# 5-Connector.net
KiCad netlist of a schematic drawn in Altium Designer
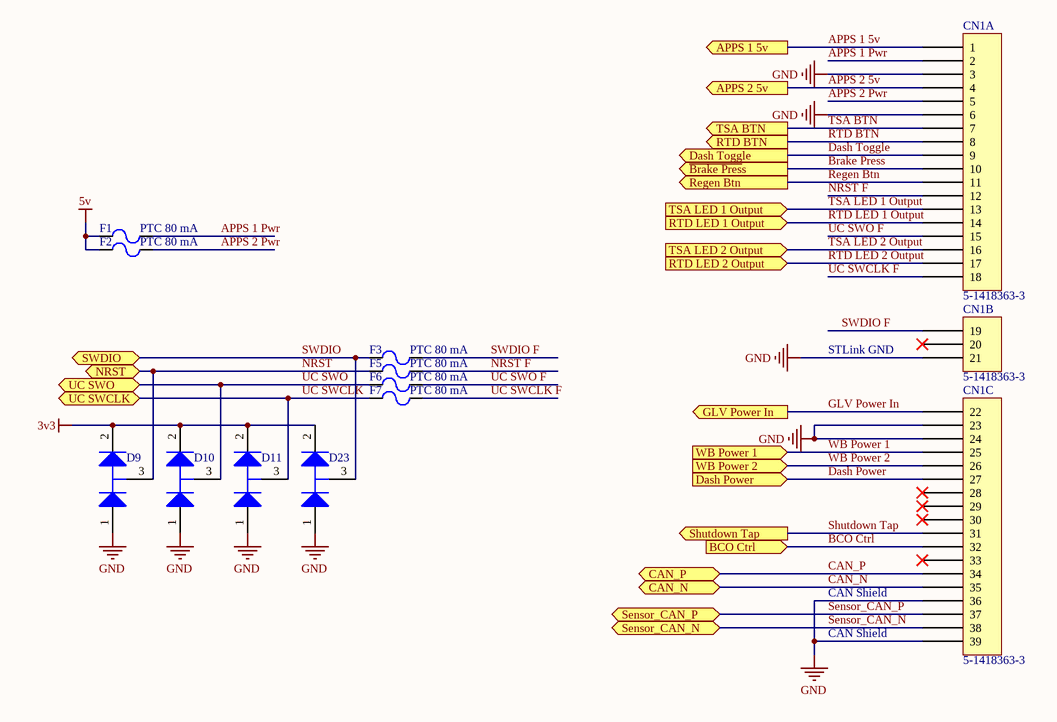
[diagram p0: 5-Connector.SchDoc]

(export (version "E")
  (design (tool "Eeschema 10.0.6"))
  (components
    (comp (ref "CN1")
      (value "5-1418363-3")
      (footprint "5-1418363-3")
      (description "Levyseal 90 degree 39 pin header")
      (libsource (lib "VCB20") (part "5-1418363-3"))
    )
    (comp (ref "D9")
      (value "SZNUP1301ML3T1G")
      (footprint "ONSC-SOT-23-3-318-08_V")
      (fields (field (name "MANUFACTURER") "On Semiconductor"))
      (libsource (lib "Altium Content Vault") (part "ONSC-NUP1301-SOT-23-3-318-08"))
    )
    (comp (ref "D10")
      (value "SZNUP1301ML3T1G")
      (footprint "ONSC-SOT-23-3-318-08_V")
      (fields (field (name "MANUFACTURER") "On Semiconductor"))
      (libsource (lib "Altium Content Vault") (part "ONSC-NUP1301-SOT-23-3-318-08"))
    )
    (comp (ref "D11")
      (value "SZNUP1301ML3T1G")
      (footprint "ONSC-SOT-23-3-318-08_V")
      (fields (field (name "MANUFACTURER") "On Semiconductor"))
      (libsource (lib "Altium Content Vault") (part "ONSC-NUP1301-SOT-23-3-318-08"))
    )
    (comp (ref "D23")
      (value "SZNUP1301ML3T1G")
      (footprint "ONSC-SOT-23-3-318-08_V")
      (fields (field (name "MANUFACTURER") "On Semiconductor"))
      (libsource (lib "Altium Content Vault") (part "ONSC-NUP1301-SOT-23-3-318-08"))
    )
    (comp (ref "F1")
      (value "PTC 80 mA")
      (footprint "0603 fuse")
      (description "0ZCM0008FF2G")
      (libsource (lib "VCU Library") (part "PTC fuse 80mA 0ZCM0008FF2G"))
    )
    (comp (ref "F2")
      (value "PTC 80 mA")
      (footprint "0603 fuse")
      (description "0ZCM0008FF2G")
      (libsource (lib "VCU Library") (part "PTC fuse 80mA 0ZCM0008FF2G"))
    )
    (comp (ref "F3")
      (value "PTC 80 mA")
      (footprint "0603 fuse")
      (description "0ZCM0008FF2G")
      (libsource (lib "VCU Library") (part "PTC fuse 80mA 0ZCM0008FF2G"))
    )
    (comp (ref "F5")
      (value "PTC 80 mA")
      (footprint "0603 fuse")
      (description "0ZCM0008FF2G")
      (libsource (lib "VCU Library") (part "PTC fuse 80mA 0ZCM0008FF2G"))
    )
    (comp (ref "F6")
      (value "PTC 80 mA")
      (footprint "0603 fuse")
      (description "0ZCM0008FF2G")
      (libsource (lib "VCU Library") (part "PTC fuse 80mA 0ZCM0008FF2G"))
    )
    (comp (ref "F7")
      (value "PTC 80 mA")
      (footprint "0603 fuse")
      (description "0ZCM0008FF2G")
      (libsource (lib "VCU Library") (part "PTC fuse 80mA 0ZCM0008FF2G"))
    )
  )
  (nets
    (net (code "1") (name "/APPS 1 5v") (class "Default")
      (node (ref "CN1") (pin "1") (pinfunction "1_1") (pintype "passive"))
    )
    (net (code "2") (name "/APPS 1 Pwr") (class "Default")
      (node (ref "CN1") (pin "2") (pinfunction "2_2") (pintype "passive"))
      (node (ref "F1") (pin "2") (pinfunction "2_2") (pintype "passive"))
    )
    (net (code "3") (name "/APPS 2 5v") (class "Default")
      (node (ref "CN1") (pin "4") (pinfunction "4_4") (pintype "passive"))
    )
    (net (code "4") (name "/APPS 2 Pwr") (class "Default")
      (node (ref "CN1") (pin "5") (pinfunction "5_5") (pintype "passive"))
      (node (ref "F2") (pin "2") (pinfunction "2_2") (pintype "passive"))
    )
    (net (code "5") (name "/BCO Ctrl") (class "Default")
      (node (ref "CN1") (pin "32") (pinfunction "32_32") (pintype "passive"))
    )
    (net (code "6") (name "/CAN_N") (class "Default")
      (node (ref "CN1") (pin "35") (pinfunction "35_35") (pintype "passive"))
    )
    (net (code "7") (name "/CAN_P") (class "Default")
      (node (ref "CN1") (pin "34") (pinfunction "34_34") (pintype "passive"))
    )
    (net (code "8") (name "/Dash Power") (class "Default")
      (node (ref "CN1") (pin "27") (pinfunction "27_27") (pintype "passive"))
    )
    (net (code "9") (name "/Dash Toggle") (class "Default")
      (node (ref "CN1") (pin "9") (pinfunction "9_9") (pintype "passive"))
    )
    (net (code "10") (name "/GLV Power In") (class "Default")
      (node (ref "CN1") (pin "22") (pinfunction "22_22") (pintype "passive"))
    )
    (net (code "11") (name "/NRST") (class "Default")
      (node (ref "D9") (pin "3") (pinfunction "K/A_3") (pintype "passive"))
      (node (ref "F5") (pin "1") (pinfunction "1_1") (pintype "passive"))
    )
    (net (code "12") (name "/NRST F") (class "Default")
      (node (ref "CN1") (pin "12") (pinfunction "12_12") (pintype "passive"))
      (node (ref "F5") (pin "2") (pinfunction "2_2") (pintype "passive"))
    )
    (net (code "13") (name "/RTD BTN") (class "Default")
      (node (ref "CN1") (pin "8") (pinfunction "8_8") (pintype "passive"))
    )
    (net (code "14") (name "/RTD LED 1 Output") (class "Default")
      (node (ref "CN1") (pin "14") (pinfunction "14_14") (pintype "passive"))
    )
    (net (code "15") (name "/RTD LED 2 Output") (class "Default")
      (node (ref "CN1") (pin "17") (pinfunction "17_17") (pintype "passive"))
    )
    (net (code "16") (name "/Regen Btn") (class "Default")
      (node (ref "CN1") (pin "11") (pinfunction "11_11") (pintype "passive"))
    )
    (net (code "17") (name "/SWDIO") (class "Default")
      (node (ref "D23") (pin "3") (pinfunction "K/A_3") (pintype "passive"))
      (node (ref "F3") (pin "1") (pinfunction "1_1") (pintype "passive"))
    )
    (net (code "18") (name "/SWDIO F") (class "Default")
      (node (ref "CN1") (pin "19") (pinfunction "19_19") (pintype "passive"))
      (node (ref "F3") (pin "2") (pinfunction "2_2") (pintype "passive"))
    )
    (net (code "19") (name "/Sensor_CAN_N") (class "Default")
      (node (ref "CN1") (pin "38") (pinfunction "38_38") (pintype "passive"))
    )
    (net (code "20") (name "/Sensor_CAN_P") (class "Default")
      (node (ref "CN1") (pin "37") (pinfunction "37_37") (pintype "passive"))
    )
    (net (code "21") (name "/Shutdown Tap") (class "Default")
      (node (ref "CN1") (pin "31") (pinfunction "31_31") (pintype "passive"))
    )
    (net (code "22") (name "/TSA BTN") (class "Default")
      (node (ref "CN1") (pin "7") (pinfunction "7_7") (pintype "passive"))
    )
    (net (code "23") (name "/TSA LED 1 Output") (class "Default")
      (node (ref "CN1") (pin "13") (pinfunction "13_13") (pintype "passive"))
    )
    (net (code "24") (name "/TSA LED 2 Output") (class "Default")
      (node (ref "CN1") (pin "16") (pinfunction "16_16") (pintype "passive"))
    )
    (net (code "25") (name "/UC SWCLK") (class "Default")
      (node (ref "D11") (pin "3") (pinfunction "K/A_3") (pintype "passive"))
      (node (ref "F7") (pin "1") (pinfunction "1_1") (pintype "passive"))
    )
    (net (code "26") (name "/UC SWCLK F") (class "Default")
      (node (ref "CN1") (pin "18") (pinfunction "18_18") (pintype "passive"))
      (node (ref "F7") (pin "2") (pinfunction "2_2") (pintype "passive"))
    )
    (net (code "27") (name "/UC SWO") (class "Default")
      (node (ref "D10") (pin "3") (pinfunction "K/A_3") (pintype "passive"))
      (node (ref "F6") (pin "1") (pinfunction "1_1") (pintype "passive"))
    )
    (net (code "28") (name "/UC SWO F") (class "Default")
      (node (ref "CN1") (pin "15") (pinfunction "15_15") (pintype "passive"))
      (node (ref "F6") (pin "2") (pinfunction "2_2") (pintype "passive"))
    )
    (net (code "29") (name "/WB Power 1") (class "Default")
      (node (ref "CN1") (pin "25") (pinfunction "25_25") (pintype "passive"))
    )
    (net (code "30") (name "/WB Power 2") (class "Default")
      (node (ref "CN1") (pin "26") (pinfunction "26_26") (pintype "passive"))
    )
    (net (code "31") (name "/~{Brake Pres}s") (class "Default")
      (node (ref "CN1") (pin "10") (pinfunction "10_10") (pintype "passive"))
    )
    (net (code "32") (name "3v3") (class "Default")
      (node (ref "D10") (pin "2") (pinfunction "K_2") (pintype "passive"))
      (node (ref "D11") (pin "2") (pinfunction "K_2") (pintype "passive"))
      (node (ref "D23") (pin "2") (pinfunction "K_2") (pintype "passive"))
      (node (ref "D9") (pin "2") (pinfunction "K_2") (pintype "passive"))
    )
    (net (code "33") (name "5v") (class "Default")
      (node (ref "F1") (pin "1") (pinfunction "1_1") (pintype "passive"))
      (node (ref "F2") (pin "1") (pinfunction "1_1") (pintype "passive"))
    )
    (net (code "34") (name "GND") (class "Default")
      (node (ref "CN1") (pin "21") (pinfunction "21_21") (pintype "passive"))
      (node (ref "CN1") (pin "23") (pinfunction "23_23") (pintype "passive"))
      (node (ref "CN1") (pin "24") (pinfunction "24_24") (pintype "passive"))
      (node (ref "CN1") (pin "3") (pinfunction "3_3") (pintype "passive"))
      (node (ref "CN1") (pin "36") (pinfunction "36_36") (pintype "passive"))
      (node (ref "CN1") (pin "39") (pinfunction "39_39") (pintype "passive"))
      (node (ref "CN1") (pin "6") (pinfunction "6_6") (pintype "passive"))
      (node (ref "D10") (pin "1") (pinfunction "A_1") (pintype "passive"))
      (node (ref "D11") (pin "1") (pinfunction "A_1") (pintype "passive"))
      (node (ref "D23") (pin "1") (pinfunction "A_1") (pintype "passive"))
      (node (ref "D9") (pin "1") (pinfunction "A_1") (pintype "passive"))
    )
    (net (code "35") (name "unconnected-(CN1-Pad20)") (class "Default")
      (node (ref "CN1") (pin "20") (pinfunction "20_20") (pintype "passive+no_connect"))
    )
    (net (code "36") (name "unconnected-(CN1-Pad28)") (class "Default")
      (node (ref "CN1") (pin "28") (pinfunction "28_28") (pintype "passive+no_connect"))
    )
    (net (code "37") (name "unconnected-(CN1-Pad29)") (class "Default")
      (node (ref "CN1") (pin "29") (pinfunction "29_29") (pintype "passive+no_connect"))
    )
    (net (code "38") (name "unconnected-(CN1-Pad30)") (class "Default")
      (node (ref "CN1") (pin "30") (pinfunction "30_30") (pintype "passive+no_connect"))
    )
    (net (code "39") (name "unconnected-(CN1-Pad33)") (class "Default")
      (node (ref "CN1") (pin "33") (pinfunction "33_33") (pintype "passive+no_connect"))
    )
  )
)
